# CH32V305GBU6-R0.net
KiCad netlist of a schematic drawn in Altium Designer
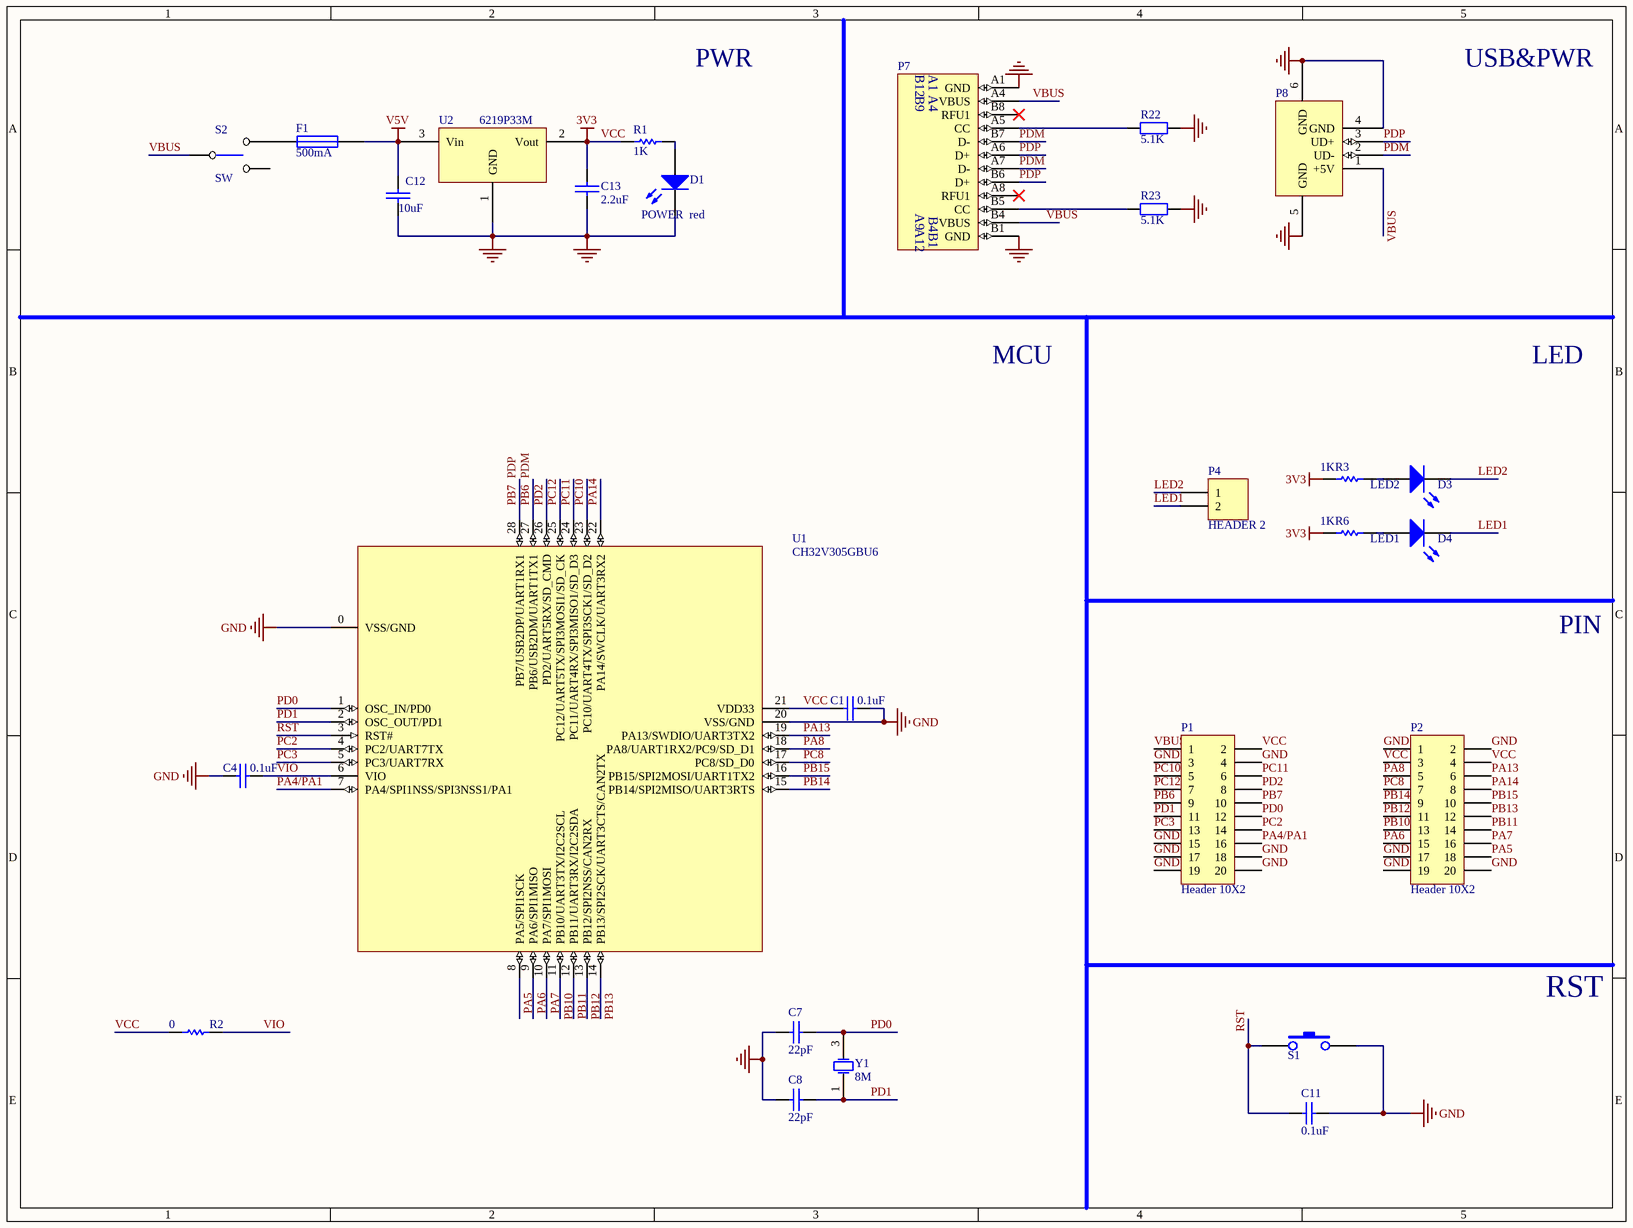
[diagram p0: CH32V305GBU6-R0.SchDoc]

(export (version "E")
  (design (tool "Eeschema 10.0.6"))
  (components
    (comp (ref "C1")
      (value "0.1uF")
      (footprint "0603_C")
      (description "Capacitor")
      (libsource (lib "*") (part "CAP"))
    )
    (comp (ref "C4")
      (value "0.1uF")
      (footprint "0603_C")
      (description "Capacitor")
      (libsource (lib "*") (part "CAP"))
    )
    (comp (ref "C7")
      (value "22pF")
      (footprint "0603_C")
      (description "Capacitor")
      (fields (field (name "PUBLISHER") "Altium Limited"))
      (libsource (lib "*") (part "Cap"))
    )
    (comp (ref "C8")
      (value "22pF")
      (footprint "0603_C")
      (description "Capacitor")
      (fields (field (name "PUBLISHER") "Altium Limited"))
      (libsource (lib "*") (part "Cap"))
    )
    (comp (ref "C11")
      (value "0.1uF")
      (footprint "0603_C")
      (description "Capacitor")
      (libsource (lib "Miscellaneous Devices") (part "Cap"))
    )
    (comp (ref "C12")
      (value "10uF")
      (footprint "0603_C")
      (description "Capacitor")
      (libsource (lib "*") (part "CAP"))
    )
    (comp (ref "C13")
      (value "2.2uF")
      (footprint "0603_C")
      (description "Capacitor")
      (libsource (lib "*") (part "CAP"))
    )
    (comp (ref "D1")
      (value "POWER  red")
      (footprint "0603+")
      (description "Typical INFRARED GaAs LED")
      (fields (field (name "PUBLISHER") "Altium Limited"))
      (libsource (lib "*") (part "LED0"))
    )
    (comp (ref "D3")
      (value "LED2")
      (footprint "0603+")
      (description "Typical INFRARED GaAs LED")
      (fields (field (name "PUBLISHER") "Altium Limited"))
      (libsource (lib "*") (part "LED0"))
    )
    (comp (ref "D4")
      (value "LED1")
      (footprint "0603+")
      (description "Typical INFRARED GaAs LED")
      (fields (field (name "PUBLISHER") "Altium Limited"))
      (libsource (lib "*") (part "LED0"))
    )
    (comp (ref "F1")
      (value "500mA")
      (footprint "0603")
      (description "Fuse")
      (libsource (lib "*") (part "FUSE1"))
    )
    (comp (ref "P1")
      (value "Header 10X2")
      (footprint "IDC20-2.54mm")
      (description "Header, 10-Pin, Dual row")
      (fields (field (name "PUBLISHER") "Altium Limited"))
      (libsource (lib "Miscellaneous Connectors") (part "Header 10X2"))
    )
    (comp (ref "P2")
      (value "Header 10X2")
      (footprint "IDC20-2.54mm")
      (description "Header, 10-Pin, Dual row")
      (fields (field (name "PUBLISHER") "Altium Limited"))
      (libsource (lib "Miscellaneous Connectors") (part "Header 10X2"))
    )
    (comp (ref "P4")
      (value "HEADER 2")
      (footprint "SIP2-2.54mm")
      (description "Header, 2-Pin")
      (libsource (lib "wch_sch_others") (part "HEADER 2"))
    )
    (comp (ref "P7")
      (value "TYPE-C")
      (footprint "TYPE-C-Receptacle-2.0")
      (libsource (lib "*") (part "TYPE-C1"))
    )
    (comp (ref "P8")
      (value "USB_A")
      (footprint "USBAF")
      (description "USB Port")
      (libsource (lib "*") (part "USB"))
    )
    (comp (ref "R1")
      (value "1K")
      (footprint "0603")
      (description "Semiconductor Resistor")
      (fields (field (name "PUBLISHER") "Altium Limited"))
      (libsource (lib "*") (part "Res Semi"))
    )
    (comp (ref "R2")
      (value "0")
      (footprint "0603")
      (description "Semiconductor Resistor")
      (libsource (lib "*") (part "Res Semi"))
    )
    (comp (ref "R3")
      (value "1K")
      (footprint "0603")
      (description "Semiconductor Resistor")
      (libsource (lib "*") (part "Res Semi"))
    )
    (comp (ref "R6")
      (value "1K")
      (footprint "0603")
      (description "Semiconductor Resistor")
      (libsource (lib "*") (part "Res Semi"))
    )
    (comp (ref "R22")
      (value "5.1K")
      (footprint "0603")
      (description "Resistor")
      (libsource (lib "Miscellaneous Devices") (part "Res2"))
    )
    (comp (ref "R23")
      (value "5.1K")
      (footprint "0603")
      (description "Resistor")
      (libsource (lib "Miscellaneous Devices") (part "Res2"))
    )
    (comp (ref "S1") (value "RST") (footprint "SMD_6.1x3.65x2.5mm-KEY") (libsource (lib "*") (part "KEY")))
    (comp (ref "S2") (value "SW") (footprint "SW1") (libsource (lib "*") (part "SW")))
    (comp (ref "U1")
      (value "CH32V305GBU6")
      (footprint "QFN28_4X4")
      (description "RISC-V MCU, 144MHz, USB_480M, CAN, UART*4, SPI*3, SDIO")
      (libsource (lib "DHXXXSCH") (part "CH32V305GBU6"))
    )
    (comp (ref "U2")
      (value "6219P33M")
      (footprint "SOT-23")
      (libsource (lib "wch_sch_others") (part "6219P33M"))
    )
    (comp (ref "Y1")
      (value "8M")
      (footprint "XT3225")
      (description "Crystal Oscillator")
      (fields (field (name "PUBLISHER") "Altium Limited"))
      (libsource (lib "*") (part "XTAL"))
    )
  )
  (nets
    (net (code "2") (name "/LED1") (class "Default")
      (node (ref "D4") (pin "2") (pinfunction "K_2") (pintype "passive"))
      (node (ref "P4") (pin "2") (pinfunction "2_2") (pintype "passive"))
    )
    (net (code "3") (name "/LED2") (class "Default")
      (node (ref "D3") (pin "2") (pinfunction "K_2") (pintype "passive"))
      (node (ref "P4") (pin "1") (pinfunction "1_1") (pintype "passive"))
    )
    (net (code "4") (name "/PA4{slash}PA1") (class "Default")
      (node (ref "P1") (pin "16") (pinfunction "16_16") (pintype "passive"))
      (node (ref "U1") (pin "7") (pinfunction "PA4/SPI1NSS/SPI3NSS1/PA1_7") (pintype "bidirectional"))
    )
    (net (code "5") (name "/PA5") (class "Default")
      (node (ref "P2") (pin "18") (pinfunction "18_18") (pintype "passive"))
      (node (ref "U1") (pin "8") (pinfunction "PA5/SPI1SCK_8") (pintype "bidirectional"))
    )
    (net (code "6") (name "/PA6") (class "Default")
      (node (ref "P2") (pin "15") (pinfunction "15_15") (pintype "passive"))
      (node (ref "U1") (pin "9") (pinfunction "PA6/SPI1MISO_9") (pintype "bidirectional"))
    )
    (net (code "7") (name "/PA7") (class "Default")
      (node (ref "P2") (pin "16") (pinfunction "16_16") (pintype "passive"))
      (node (ref "U1") (pin "10") (pinfunction "PA7/SPI1MOSI_10") (pintype "bidirectional"))
    )
    (net (code "8") (name "/PA8") (class "Default")
      (node (ref "P2") (pin "5") (pinfunction "5_5") (pintype "passive"))
      (node (ref "U1") (pin "18") (pinfunction "PA8/UART1RX2/PC9/SD_D1_18") (pintype "bidirectional"))
    )
    (net (code "9") (name "/PA13") (class "Default")
      (node (ref "P2") (pin "6") (pinfunction "6_6") (pintype "passive"))
      (node (ref "U1") (pin "19") (pinfunction "PA13/SWDIO/UART3TX2_19") (pintype "bidirectional"))
    )
    (net (code "10") (name "/PA14") (class "Default")
      (node (ref "P2") (pin "8") (pinfunction "8_8") (pintype "passive"))
      (node (ref "U1") (pin "22") (pinfunction "PA14/SWCLK/UART3RX2_22") (pintype "bidirectional"))
    )
    (net (code "11") (name "/PB6") (class "Default")
      (node (ref "P1") (pin "9") (pinfunction "9_9") (pintype "passive"))
      (node (ref "P7") (pin "A7") (pinfunction "D-_A7") (pintype "bidirectional"))
      (node (ref "P7") (pin "B7") (pinfunction "D-_B7") (pintype "bidirectional"))
      (node (ref "P8") (pin "2") (pinfunction "UD-_2") (pintype "bidirectional"))
      (node (ref "U1") (pin "27") (pinfunction "PB6/USB2DM/UART1TX1_27") (pintype "bidirectional"))
    )
    (net (code "12") (name "/PB7") (class "Default")
      (node (ref "P1") (pin "10") (pinfunction "10_10") (pintype "passive"))
      (node (ref "P7") (pin "A6") (pinfunction "D+_A6") (pintype "bidirectional"))
      (node (ref "P7") (pin "B6") (pinfunction "D+_B6") (pintype "bidirectional"))
      (node (ref "P8") (pin "3") (pinfunction "UD+_3") (pintype "bidirectional"))
      (node (ref "U1") (pin "28") (pinfunction "PB7/USB2DP/UART1RX1_28") (pintype "bidirectional"))
    )
    (net (code "13") (name "/PB10") (class "Default")
      (node (ref "P2") (pin "13") (pinfunction "13_13") (pintype "passive"))
      (node (ref "U1") (pin "11") (pinfunction "PB10/UART3TX/I2C2SCL_11") (pintype "bidirectional"))
    )
    (net (code "14") (name "/PB11") (class "Default")
      (node (ref "P2") (pin "14") (pinfunction "14_14") (pintype "passive"))
      (node (ref "U1") (pin "12") (pinfunction "PB11/UART3RX/I2C2SDA_12") (pintype "bidirectional"))
    )
    (net (code "15") (name "/PB12") (class "Default")
      (node (ref "P2") (pin "11") (pinfunction "11_11") (pintype "passive"))
      (node (ref "U1") (pin "13") (pinfunction "PB12/SPI2NSS/CAN2RX_13") (pintype "bidirectional"))
    )
    (net (code "16") (name "/PB13") (class "Default")
      (node (ref "P2") (pin "12") (pinfunction "12_12") (pintype "passive"))
      (node (ref "U1") (pin "14") (pinfunction "PB13/SPI2SCK/UART3CTS/CAN2TX_14") (pintype "bidirectional"))
    )
    (net (code "17") (name "/PB14") (class "Default")
      (node (ref "P2") (pin "9") (pinfunction "9_9") (pintype "passive"))
      (node (ref "U1") (pin "15") (pinfunction "PB14/SPI2MISO/UART3RTS_15") (pintype "bidirectional"))
    )
    (net (code "18") (name "/PB15") (class "Default")
      (node (ref "P2") (pin "10") (pinfunction "10_10") (pintype "passive"))
      (node (ref "U1") (pin "16") (pinfunction "PB15/SPI2MOSI/UART1TX2_16") (pintype "bidirectional"))
    )
    (net (code "19") (name "/PC2") (class "Default")
      (node (ref "P1") (pin "14") (pinfunction "14_14") (pintype "passive"))
      (node (ref "U1") (pin "4") (pinfunction "PC2/UART7TX_4") (pintype "bidirectional"))
    )
    (net (code "20") (name "/PC3") (class "Default")
      (node (ref "P1") (pin "13") (pinfunction "13_13") (pintype "passive"))
      (node (ref "U1") (pin "5") (pinfunction "PC3/UART7RX_5") (pintype "bidirectional"))
    )
    (net (code "21") (name "/PC8") (class "Default")
      (node (ref "P2") (pin "7") (pinfunction "7_7") (pintype "passive"))
      (node (ref "U1") (pin "17") (pinfunction "PC8/SD_D0_17") (pintype "bidirectional"))
    )
    (net (code "22") (name "/PC10") (class "Default")
      (node (ref "P1") (pin "5") (pinfunction "5_5") (pintype "passive"))
      (node (ref "U1") (pin "23") (pinfunction "PC10/UART4TX/SPI3SCK1/SD_D2_23") (pintype "bidirectional"))
    )
    (net (code "23") (name "/PC11") (class "Default")
      (node (ref "P1") (pin "6") (pinfunction "6_6") (pintype "passive"))
      (node (ref "U1") (pin "24") (pinfunction "PC11/UART4RX/SPI3MISO1/SD_D3_24") (pintype "bidirectional"))
    )
    (net (code "24") (name "/PC12") (class "Default")
      (node (ref "P1") (pin "7") (pinfunction "7_7") (pintype "passive"))
      (node (ref "U1") (pin "25") (pinfunction "PC12/UART5TX/SPI3MOSI1/SD_CK_25") (pintype "bidirectional"))
    )
    (net (code "25") (name "/PD0") (class "Default")
      (node (ref "C7") (pin "2") (pinfunction "2_2") (pintype "passive"))
      (node (ref "P1") (pin "12") (pinfunction "12_12") (pintype "passive"))
      (node (ref "U1") (pin "1") (pinfunction "OSC_IN/PD0_1") (pintype "bidirectional"))
      (node (ref "Y1") (pin "3") (pinfunction "OSC2_3") (pintype "passive"))
    )
    (net (code "26") (name "/PD1") (class "Default")
      (node (ref "C8") (pin "2") (pinfunction "2_2") (pintype "passive"))
      (node (ref "P1") (pin "11") (pinfunction "11_11") (pintype "passive"))
      (node (ref "U1") (pin "2") (pinfunction "OSC_OUT/PD1_2") (pintype "bidirectional"))
      (node (ref "Y1") (pin "1") (pinfunction "OSC1_1") (pintype "passive"))
    )
    (net (code "27") (name "/PD2") (class "Default")
      (node (ref "P1") (pin "8") (pinfunction "8_8") (pintype "passive"))
      (node (ref "U1") (pin "26") (pinfunction "PD2/UART5RX/SD_CMD_26") (pintype "bidirectional"))
    )
    (net (code "28") (name "/RST") (class "Default")
      (node (ref "C11") (pin "2") (pinfunction "2_2") (pintype "passive"))
      (node (ref "S1") (pin "1") (pinfunction "1_1") (pintype "passive"))
      (node (ref "U1") (pin "3") (pinfunction "RST#_3") (pintype "input"))
    )
    (net (code "29") (name "/VBUS") (class "Default")
      (node (ref "P1") (pin "1") (pinfunction "1_1") (pintype "passive"))
      (node (ref "P7") (pin "A4") (pinfunction "VBUS_A4") (pintype "bidirectional"))
      (node (ref "P7") (pin "B4") (pinfunction "VBUS_B4") (pintype "bidirectional"))
      (node (ref "P8") (pin "1") (pinfunction "+5V_1") (pintype "power_in"))
      (node (ref "S2") (pin "1") (pinfunction "1_1") (pintype "passive"))
    )
    (net (code "30") (name "/VIO") (class "Default")
      (node (ref "C4") (pin "1") (pinfunction "1_1") (pintype "passive"))
      (node (ref "R2") (pin "2") (pinfunction "2_2") (pintype "passive"))
      (node (ref "U1") (pin "6") (pinfunction "VIO_6") (pintype "power_in"))
    )
    (net (code "31") (name "3V3") (class "Default")
      (node (ref "C1") (pin "1") (pinfunction "1_1") (pintype "passive"))
      (node (ref "C13") (pin "1") (pinfunction "1_1") (pintype "passive"))
      (node (ref "P1") (pin "2") (pinfunction "2_2") (pintype "passive"))
      (node (ref "P2") (pin "3") (pinfunction "3_3") (pintype "passive"))
      (node (ref "P2") (pin "4") (pinfunction "4_4") (pintype "passive"))
      (node (ref "R1") (pin "2") (pinfunction "2_2") (pintype "passive"))
      (node (ref "R2") (pin "1") (pinfunction "1_1") (pintype "passive"))
      (node (ref "R3") (pin "1") (pinfunction "1_1") (pintype "passive"))
      (node (ref "R6") (pin "1") (pinfunction "1_1") (pintype "passive"))
      (node (ref "U1") (pin "21") (pinfunction "VDD33_21") (pintype "power_in"))
      (node (ref "U2") (pin "2") (pinfunction "Vout_2") (pintype "passive"))
    )
    (net (code "32") (name "GND") (class "Default")
      (node (ref "C1") (pin "2") (pinfunction "2_2") (pintype "passive"))
      (node (ref "C11") (pin "1") (pinfunction "1_1") (pintype "passive"))
      (node (ref "C12") (pin "2") (pinfunction "2_2") (pintype "passive"))
      (node (ref "C13") (pin "2") (pinfunction "2_2") (pintype "passive"))
      (node (ref "C4") (pin "2") (pinfunction "2_2") (pintype "passive"))
      (node (ref "C7") (pin "1") (pinfunction "1_1") (pintype "passive"))
      (node (ref "C8") (pin "1") (pinfunction "1_1") (pintype "passive"))
      (node (ref "D1") (pin "2") (pinfunction "K_2") (pintype "passive"))
      (node (ref "P1") (pin "15") (pinfunction "15_15") (pintype "passive"))
      (node (ref "P1") (pin "17") (pinfunction "17_17") (pintype "passive"))
      (node (ref "P1") (pin "18") (pinfunction "18_18") (pintype "passive"))
      (node (ref "P1") (pin "19") (pinfunction "19_19") (pintype "passive"))
      (node (ref "P1") (pin "20") (pinfunction "20_20") (pintype "passive"))
      (node (ref "P1") (pin "3") (pinfunction "3_3") (pintype "passive"))
      (node (ref "P1") (pin "4") (pinfunction "4_4") (pintype "passive"))
      (node (ref "P2") (pin "1") (pinfunction "1_1") (pintype "passive"))
      (node (ref "P2") (pin "17") (pinfunction "17_17") (pintype "passive"))
      (node (ref "P2") (pin "19") (pinfunction "19_19") (pintype "passive"))
      (node (ref "P2") (pin "2") (pinfunction "2_2") (pintype "passive"))
      (node (ref "P2") (pin "20") (pinfunction "20_20") (pintype "passive"))
      (node (ref "P7") (pin "A1") (pinfunction "GND_A1") (pintype "bidirectional"))
      (node (ref "P7") (pin "B1") (pinfunction "GND_B1") (pintype "bidirectional"))
      (node (ref "P8") (pin "4") (pinfunction "GND_4") (pintype "power_in"))
      (node (ref "P8") (pin "5") (pinfunction "GND_5") (pintype "power_in"))
      (node (ref "P8") (pin "6") (pinfunction "GND_6") (pintype "power_in"))
      (node (ref "R22") (pin "2") (pinfunction "2_2") (pintype "passive"))
      (node (ref "R23") (pin "2") (pinfunction "2_2") (pintype "passive"))
      (node (ref "S1") (pin "2") (pinfunction "2_2") (pintype "passive"))
      (node (ref "U1") (pin "0") (pinfunction "VSS/GND_0") (pintype "power_in"))
      (node (ref "U1") (pin "20") (pinfunction "VSS/GND_20") (pintype "power_in"))
      (node (ref "U2") (pin "1") (pinfunction "GND_1") (pintype "passive"))
    )
    (net (code "33") (name "Net-(D1-A)") (class "Default")
      (node (ref "D1") (pin "1") (pinfunction "A_1") (pintype "passive"))
      (node (ref "R1") (pin "1") (pinfunction "1_1") (pintype "passive"))
    )
    (net (code "34") (name "Net-(D3-A)") (class "Default")
      (node (ref "D3") (pin "1") (pinfunction "A_1") (pintype "passive"))
      (node (ref "R3") (pin "2") (pinfunction "2_2") (pintype "passive"))
    )
    (net (code "35") (name "Net-(D4-A)") (class "Default")
      (node (ref "D4") (pin "1") (pinfunction "A_1") (pintype "passive"))
      (node (ref "R6") (pin "2") (pinfunction "2_2") (pintype "passive"))
    )
    (net (code "36") (name "Net-(F1-Pad1)") (class "Default")
      (node (ref "F1") (pin "1") (pinfunction "1_1") (pintype "passive"))
      (node (ref "S2") (pin "3") (pinfunction "3_3") (pintype "passive"))
    )
    (net (code "37") (name "Net-(P7-CC-PadA5)") (class "Default")
      (node (ref "P7") (pin "A5") (pinfunction "CC_A5") (pintype "bidirectional"))
      (node (ref "R22") (pin "1") (pinfunction "1_1") (pintype "passive"))
    )
    (net (code "38") (name "Net-(P7-CC-PadB5)") (class "Default")
      (node (ref "P7") (pin "B5") (pinfunction "CC_B5") (pintype "bidirectional"))
      (node (ref "R23") (pin "1") (pinfunction "1_1") (pintype "passive"))
    )
    (net (code "39") (name "V5V") (class "Default")
      (node (ref "C12") (pin "1") (pinfunction "1_1") (pintype "passive"))
      (node (ref "F1") (pin "2") (pinfunction "2_2") (pintype "passive"))
      (node (ref "U2") (pin "3") (pinfunction "Vin_3") (pintype "passive"))
    )
    (net (code "40") (name "unconnected-(P7-RFU1-PadA8)") (class "Default")
      (node (ref "P7") (pin "A8") (pinfunction "RFU1_A8") (pintype "bidirectional+no_connect"))
    )
    (net (code "41") (name "unconnected-(P7-RFU1-PadB8)") (class "Default")
      (node (ref "P7") (pin "B8") (pinfunction "RFU1_B8") (pintype "bidirectional+no_connect"))
    )
    (net (code "42") (name "unconnected-(S2-Pad2)") (class "Default")
      (node (ref "S2") (pin "2") (pinfunction "2_2") (pintype "passive"))
    )
  )
)
